# BW1097_HDMI.net
KiCad netlist of a schematic drawn in Altium Designer
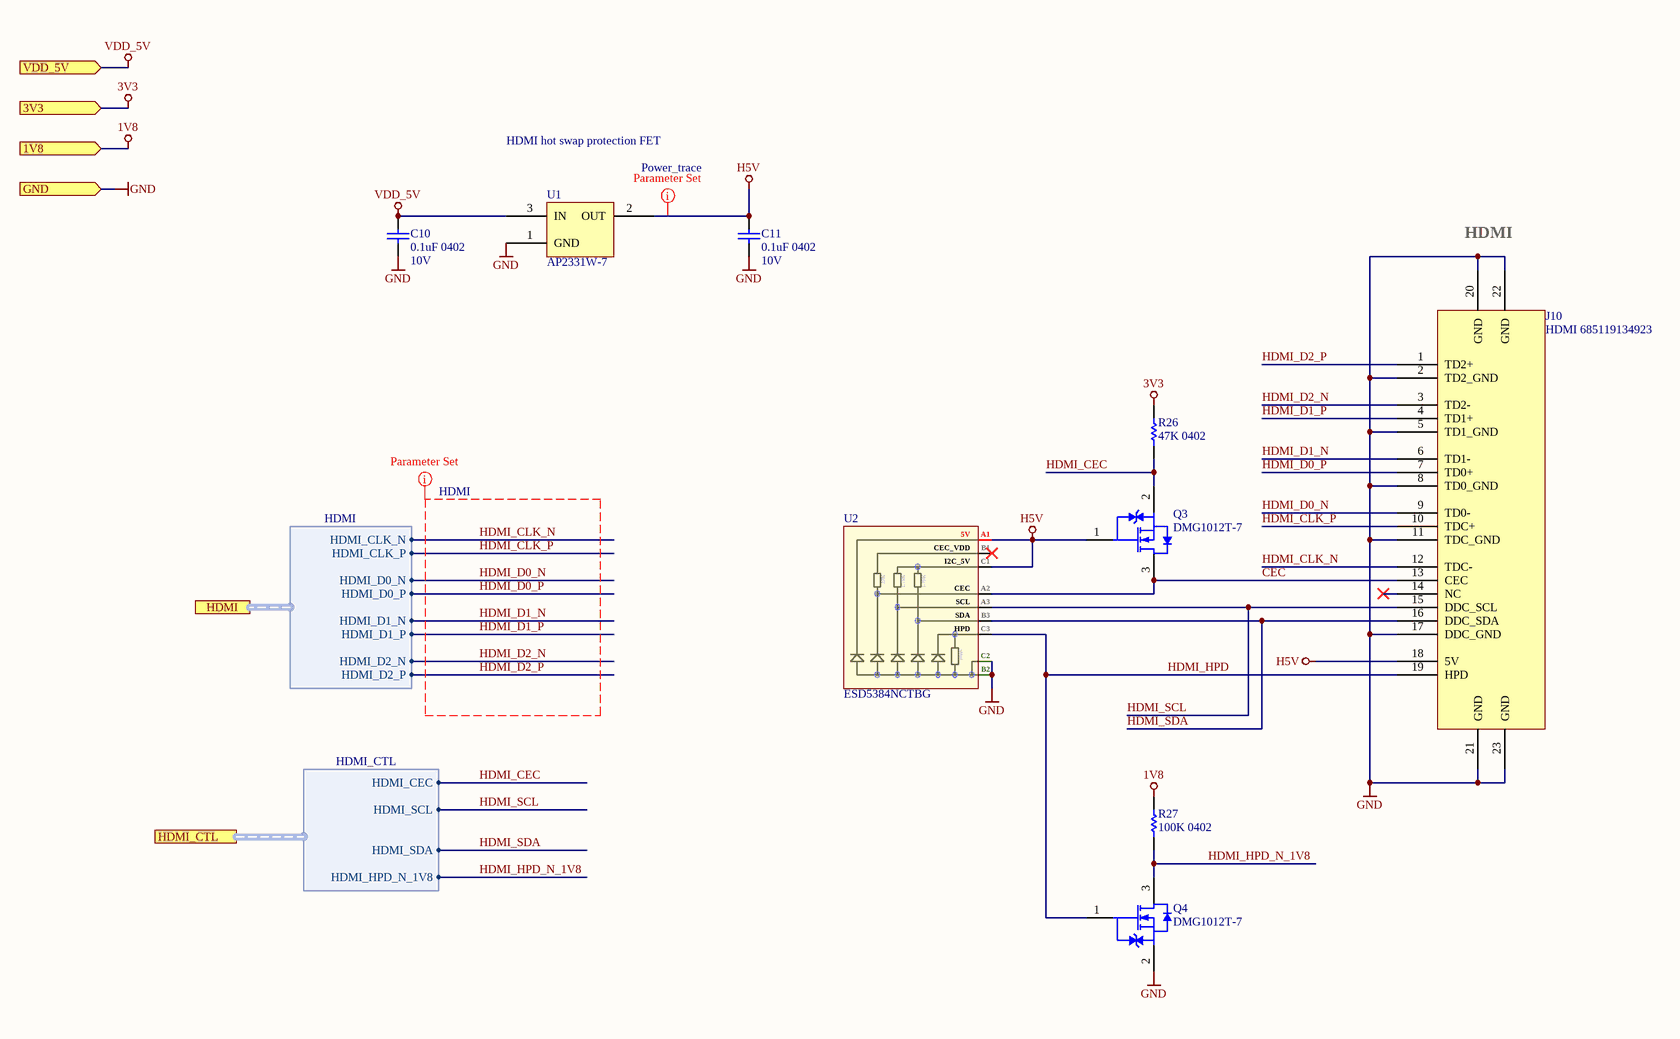
[diagram p0: BW1097_HDMI.SchDoc]

(export (version "E")
  (design (tool "Eeschema 10.0.6"))
  (components
    (comp (ref "C10")
      (value "0.1uF 0402")
      (footprint "CAP_Altium_Vault_Generic:CAPC0402(1005)70_N")
      (description "CAP CER 0.1UF 10V X7R 0402 5%")
      (fields (field (name "TOLERANCE") "5%") (field (name "VOLTAGE RATING") "10V"))
      (libsource (lib "LuxonisMaster") (part "GRM155R71A104JA01D"))
    )
    (comp (ref "C11")
      (value "0.1uF 0402")
      (footprint "CAP_Altium_Vault_Generic:CAPC0402(1005)70_N")
      (description "CAP CER 0.1UF 10V X7R 0402 5%")
      (fields (field (name "TOLERANCE") "5%") (field (name "VOLTAGE RATING") "10V"))
      (libsource (lib "LuxonisMaster") (part "GRM155R71A104JA01D"))
    )
    (comp (ref "J10")
      (value "HDMI 685119134923")
      (footprint "LuxonisMaster:685119134923")
      (description "CONN RCPT HDMI 19POS SMD R/A")
      (libsource (lib "LuxonisMaster") (part "685119134923"))
    )
    (comp (ref "Q3")
      (value "DMG1012T-7")
      (footprint "LuxonisMaster:DMG1012T-7")
      (description "MOSFET N-CH 20V 630MA SOT-523")
      (libsource (lib "LuxonisMaster") (part "DMG1012T-7"))
    )
    (comp (ref "Q4")
      (value "DMG1012T-7")
      (footprint "LuxonisMaster:DMG1012T-7")
      (description "MOSFET N-CH 20V 630MA SOT-523")
      (libsource (lib "LuxonisMaster") (part "DMG1012T-7"))
    )
    (comp (ref "R26")
      (value "47K 0402")
      (footprint "RES_Altium_Vault_Generic:RESC0402(1005)_N")
      (description "RES SMD 47K OHM 1% 1/16W 0402")
      (fields (field (name "TOLERANCE") "1%"))
      (libsource (lib "LuxonisMaster") (part "RC0402FR-0747KL"))
    )
    (comp (ref "R27")
      (value "100K 0402")
      (footprint "RES_Altium_Vault_Generic:RESC0402(1005)_N")
      (description "RES SMD 100K OHM 1% 1/16W 0402")
      (fields (field (name "TOLERANCE") "1%"))
      (libsource (lib "LuxonisMaster") (part "RC0402FR-07100KL"))
    )
    (comp (ref "U1")
      (value "AP2331W-7")
      (footprint "LuxonisMaster:AP2331W-7")
      (description "LOAD SWITCH SC59")
      (fields (field (name "VOLTAGE") "5.2V"))
      (libsource (lib "LuxonisMaster") (part "AP2331W-7"))
    )
    (comp (ref "U2")
      (value "ESD5384NCTBG")
      (footprint "LuxonisMaster:ESD5384NCTBG")
      (description "TVS DIODE 3V 9WLCSP")
      (libsource (lib "LuxonisMaster") (part "ESD5384NCTBG"))
    )
  )
  (nets
    (net (code "3") (name "/CEC") (class "Default")
      (node (ref "J10") (pin "13") (pinfunction "CEC_13") (pintype "passive"))
      (node (ref "Q3") (pin "3") (pinfunction "3_3") (pintype "passive"))
      (node (ref "U2") (pin "A2") (pinfunction "A2_A2") (pintype "passive"))
    )
    (net (code "4") (name "/HDMI_CEC") (class "Default")
      (node (ref "Q3") (pin "2") (pinfunction "2_2") (pintype "passive"))
      (node (ref "R26") (pin "1") (pinfunction "1_1") (pintype "passive"))
    )
    (net (code "5") (name "/HDMI_CLK_N") (class "Default")
      (node (ref "J10") (pin "12") (pinfunction "TDC-_12") (pintype "passive"))
    )
    (net (code "6") (name "/HDMI_CLK_P") (class "Default")
      (node (ref "J10") (pin "10") (pinfunction "TDC+_10") (pintype "passive"))
    )
    (net (code "7") (name "/HDMI_D0_N") (class "Default")
      (node (ref "J10") (pin "9") (pinfunction "TD0-_9") (pintype "passive"))
    )
    (net (code "8") (name "/HDMI_D0_P") (class "Default")
      (node (ref "J10") (pin "7") (pinfunction "TD0+_7") (pintype "passive"))
    )
    (net (code "9") (name "/HDMI_D1_N") (class "Default")
      (node (ref "J10") (pin "6") (pinfunction "TD1-_6") (pintype "passive"))
    )
    (net (code "10") (name "/HDMI_D1_P") (class "Default")
      (node (ref "J10") (pin "4") (pinfunction "TD1+_4") (pintype "passive"))
    )
    (net (code "11") (name "/HDMI_D2_N") (class "Default")
      (node (ref "J10") (pin "3") (pinfunction "TD2-_3") (pintype "passive"))
    )
    (net (code "12") (name "/HDMI_D2_P") (class "Default")
      (node (ref "J10") (pin "1") (pinfunction "TD2+_1") (pintype "passive"))
    )
    (net (code "13") (name "/HDMI_HPD") (class "Default")
      (node (ref "J10") (pin "19") (pinfunction "HPD_19") (pintype "passive"))
      (node (ref "Q4") (pin "1") (pinfunction "1_1") (pintype "passive"))
      (node (ref "U2") (pin "C3") (pinfunction "C3_C3") (pintype "passive"))
    )
    (net (code "14") (name "/HDMI_HPD_N_1V8") (class "Default")
      (node (ref "Q4") (pin "3") (pinfunction "3_3") (pintype "passive"))
      (node (ref "R27") (pin "1") (pinfunction "1_1") (pintype "passive"))
    )
    (net (code "15") (name "/HDMI_SCL") (class "Default")
      (node (ref "J10") (pin "15") (pinfunction "DDC_SCL_15") (pintype "passive"))
      (node (ref "U2") (pin "A3") (pinfunction "A3_A3") (pintype "passive"))
    )
    (net (code "16") (name "/HDMI_SDA") (class "Default")
      (node (ref "J10") (pin "16") (pinfunction "DDC_SDA_16") (pintype "passive"))
      (node (ref "U2") (pin "B3") (pinfunction "B3_B3") (pintype "passive"))
    )
    (net (code "19") (name "1V8") (class "Default")
      (node (ref "R27") (pin "2") (pinfunction "2_2") (pintype "passive"))
    )
    (net (code "20") (name "3V3") (class "Default")
      (node (ref "R26") (pin "2") (pinfunction "2_2") (pintype "passive"))
    )
    (net (code "21") (name "GND") (class "Default")
      (node (ref "C10") (pin "1") (pinfunction "1_1") (pintype "passive"))
      (node (ref "C11") (pin "1") (pinfunction "1_1") (pintype "passive"))
      (node (ref "J10") (pin "11") (pinfunction "TDC_GND_11") (pintype "passive"))
      (node (ref "J10") (pin "17") (pinfunction "DDC_GND_17") (pintype "passive"))
      (node (ref "J10") (pin "2") (pinfunction "TD2_GND_2") (pintype "passive"))
      (node (ref "J10") (pin "20") (pinfunction "GND_20") (pintype "passive"))
      (node (ref "J10") (pin "21") (pinfunction "GND_21") (pintype "passive"))
      (node (ref "J10") (pin "22") (pinfunction "GND_22") (pintype "passive"))
      (node (ref "J10") (pin "23") (pinfunction "GND_23") (pintype "passive"))
      (node (ref "J10") (pin "5") (pinfunction "TD1_GND_5") (pintype "passive"))
      (node (ref "J10") (pin "8") (pinfunction "TD0_GND_8") (pintype "passive"))
      (node (ref "Q4") (pin "2") (pinfunction "2_2") (pintype "passive"))
      (node (ref "U1") (pin "1") (pinfunction "GND_1") (pintype "passive"))
      (node (ref "U2") (pin "B2") (pinfunction "B2_B2") (pintype "passive"))
      (node (ref "U2") (pin "C2") (pinfunction "C2_C2") (pintype "passive"))
    )
    (net (code "22") (name "H5V") (class "Default")
      (node (ref "C11") (pin "2") (pinfunction "2_2") (pintype "passive"))
      (node (ref "J10") (pin "18") (pinfunction "5V_18") (pintype "passive"))
      (node (ref "Q3") (pin "1") (pinfunction "1_1") (pintype "passive"))
      (node (ref "U1") (pin "2") (pinfunction "OUT_2") (pintype "passive"))
      (node (ref "U2") (pin "A1") (pinfunction "A1_A1") (pintype "passive"))
      (node (ref "U2") (pin "C1") (pinfunction "C1_C1") (pintype "passive"))
    )
    (net (code "23") (name "VDD_5V") (class "Default")
      (node (ref "C10") (pin "2") (pinfunction "2_2") (pintype "passive"))
      (node (ref "U1") (pin "3") (pinfunction "IN_3") (pintype "passive"))
    )
    (net (code "24") (name "unconnected-(J10-NC-Pad14)") (class "Default")
      (node (ref "J10") (pin "14") (pinfunction "NC_14") (pintype "passive+no_connect"))
    )
    (net (code "25") (name "unconnected-(U2-PadB1)") (class "Default")
      (node (ref "U2") (pin "B1") (pinfunction "B1_B1") (pintype "passive+no_connect"))
    )
  )
)
